# cataclysm-TOP.net
KiCad netlist of a schematic drawn in EAGLE
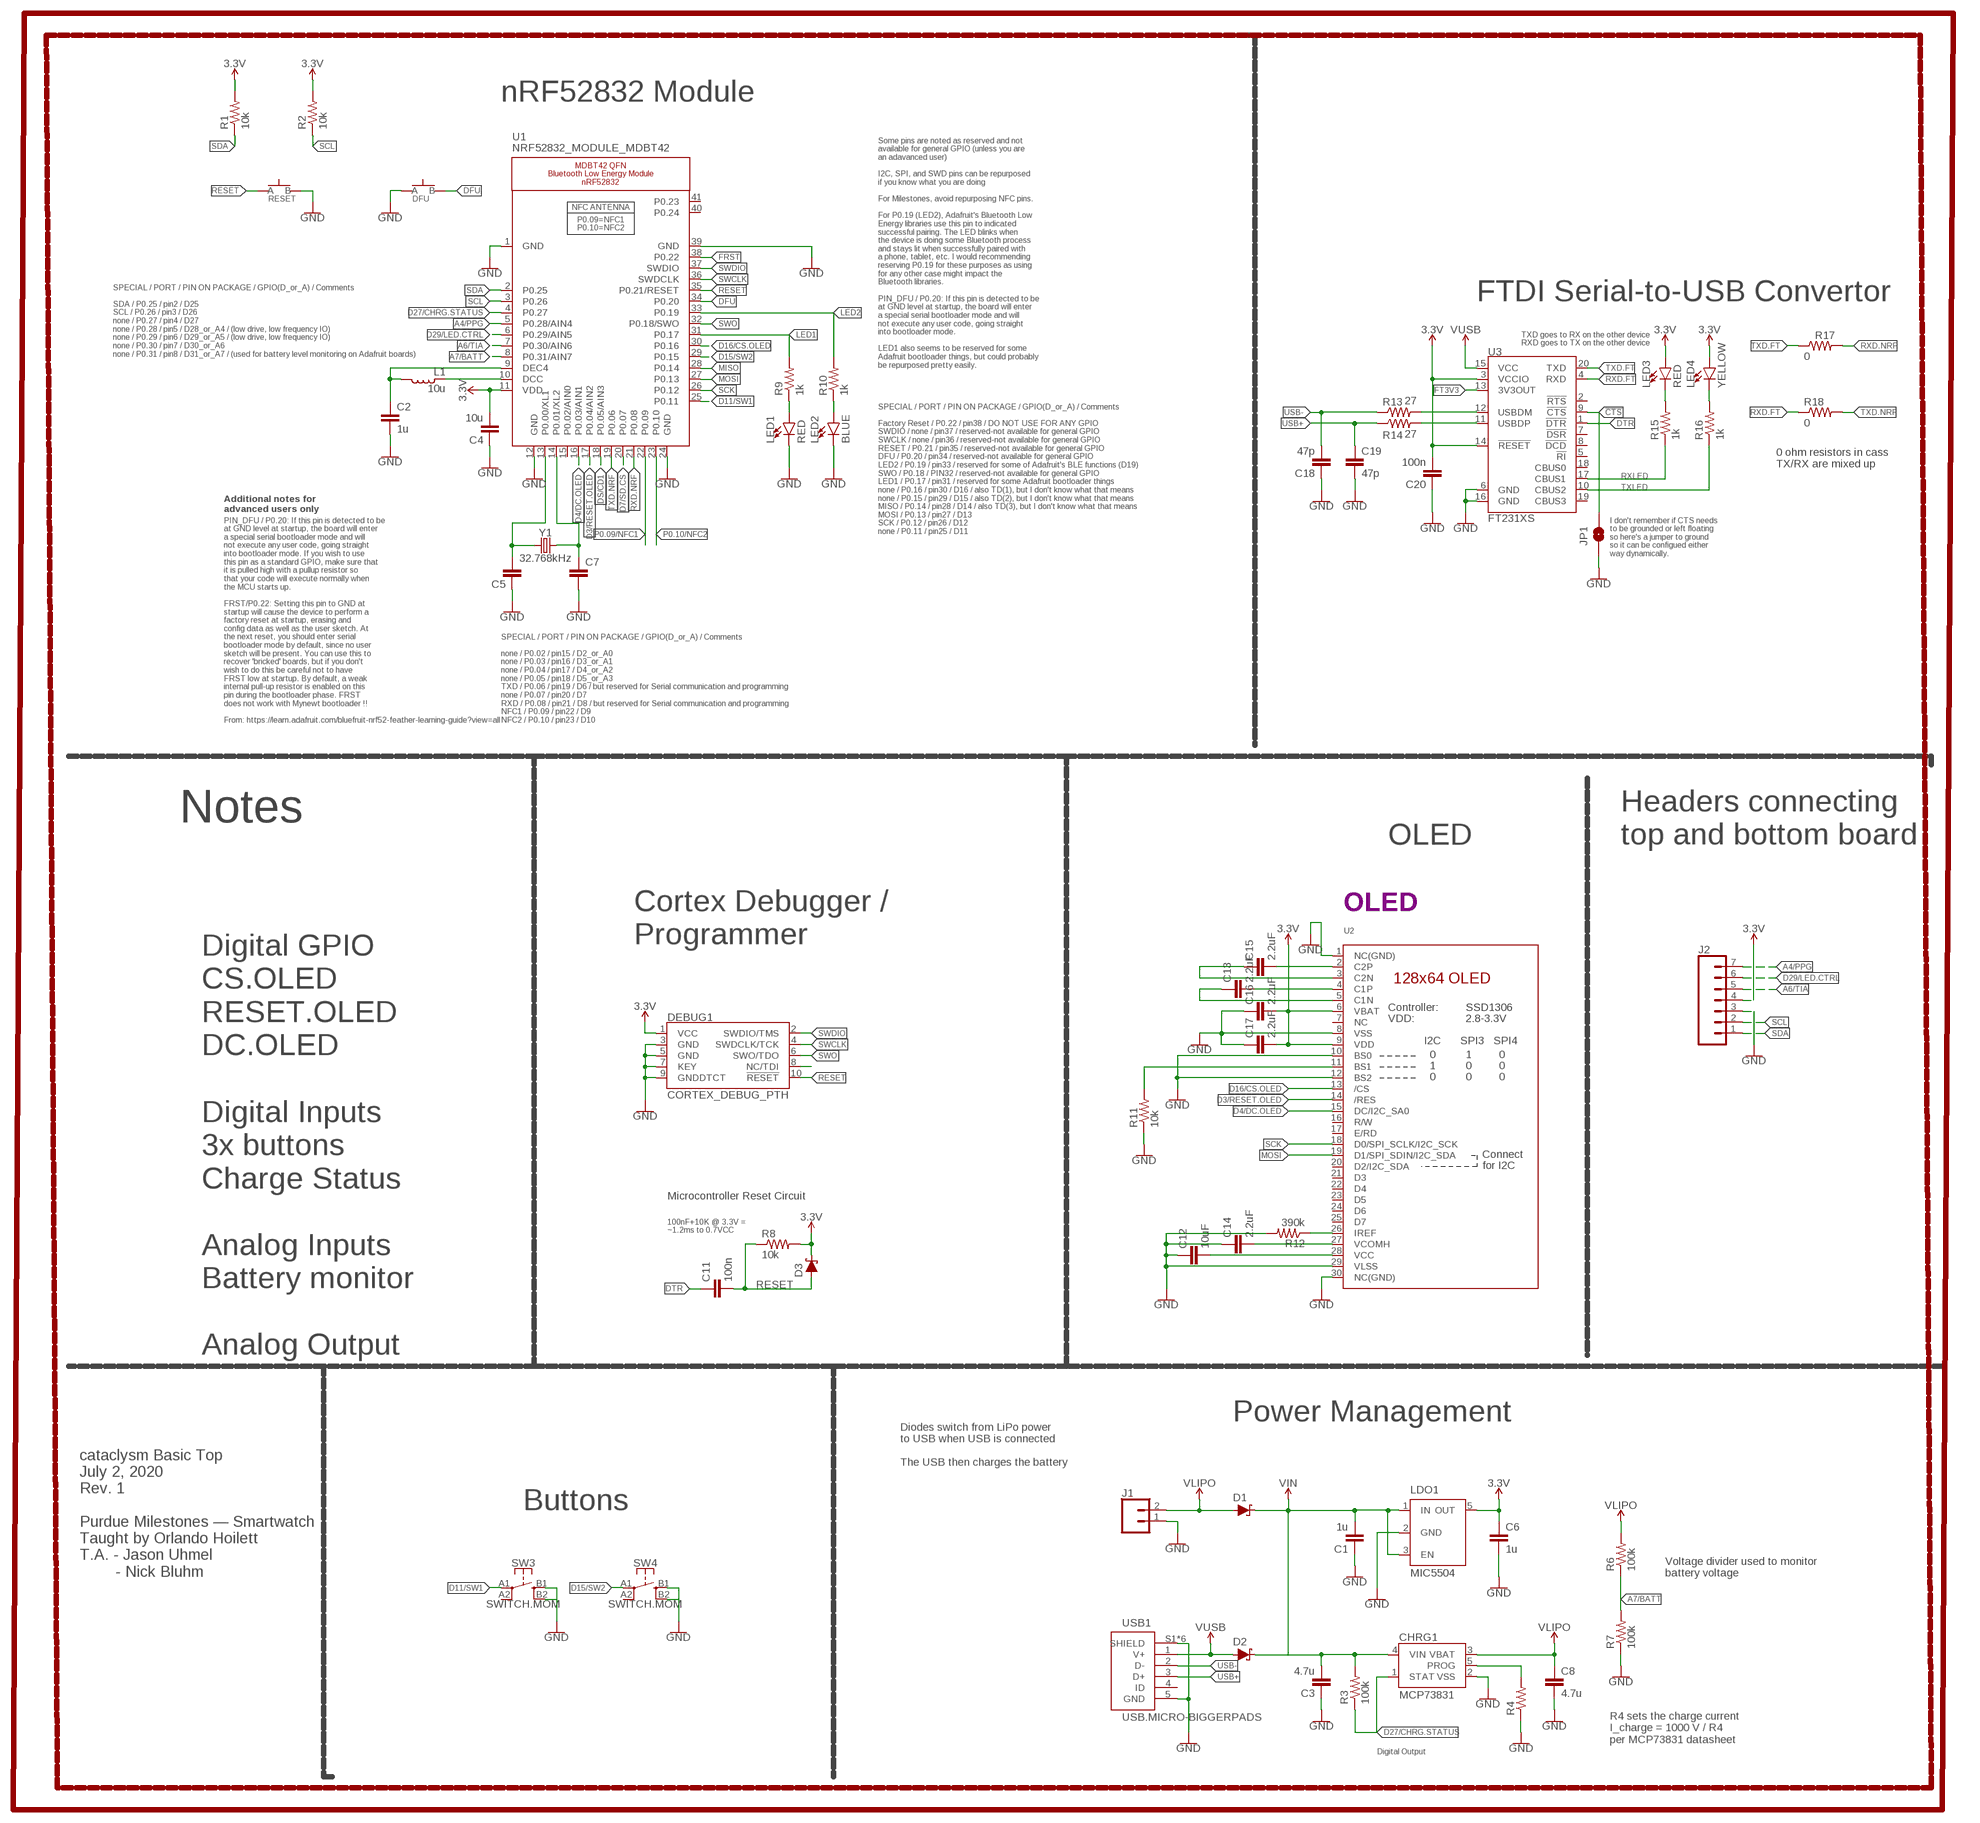
[diagram p0: schematic, sheet 1]

(export (version "E")
  (design (tool "Eeschema 10.0.6"))
  (components
    (comp (ref "C1")
      (value "1u")
      (footprint "eagle-import:C0603")
      (libsource (lib "eagle-import") (part "CAPACITOR0603"))
    )
    (comp (ref "C2")
      (value "1u")
      (footprint "eagle-import:C0603")
      (libsource (lib "eagle-import") (part "CAPACITOR0603"))
    )
    (comp (ref "C3")
      (value "4.7u")
      (footprint "eagle-import:C0603")
      (libsource (lib "eagle-import") (part "CAPACITOR0603"))
    )
    (comp (ref "C4")
      (value "10u")
      (footprint "eagle-import:C0805")
      (libsource (lib "eagle-import") (part "CAPACITOR0805"))
    )
    (comp (ref "C5")
      (value "CAPACITOR0603")
      (footprint "eagle-import:C0603")
      (libsource (lib "eagle-import") (part "CAPACITOR0603"))
    )
    (comp (ref "C6")
      (value "1u")
      (footprint "eagle-import:C0603")
      (libsource (lib "eagle-import") (part "CAPACITOR0603"))
    )
    (comp (ref "C7")
      (value "CAPACITOR0603")
      (footprint "eagle-import:C0603")
      (libsource (lib "eagle-import") (part "CAPACITOR0603"))
    )
    (comp (ref "C8")
      (value "4.7u")
      (footprint "eagle-import:C0603")
      (libsource (lib "eagle-import") (part "CAPACITOR0603"))
    )
    (comp (ref "C11")
      (value "100n")
      (footprint "eagle-import:C0603")
      (libsource (lib "eagle-import") (part "CAPACITOR0603"))
    )
    (comp (ref "C12")
      (value "10uF")
      (footprint "eagle-import:C0603")
      (libsource (lib "eagle-import") (part "CAPACITOR0603"))
    )
    (comp (ref "C13")
      (value "2.2uF")
      (footprint "eagle-import:C0402")
      (libsource (lib "eagle-import") (part "CAPACITOR0402"))
    )
    (comp (ref "C14")
      (value "2.2uF")
      (footprint "eagle-import:C0603")
      (libsource (lib "eagle-import") (part "CAPACITOR0603"))
    )
    (comp (ref "C15")
      (value "2.2uF")
      (footprint "eagle-import:C0402")
      (libsource (lib "eagle-import") (part "CAPACITOR0402"))
    )
    (comp (ref "C16")
      (value "2.2uF")
      (footprint "eagle-import:C0402")
      (libsource (lib "eagle-import") (part "CAPACITOR0402"))
    )
    (comp (ref "C17")
      (value "2.2uF")
      (footprint "eagle-import:C0402")
      (libsource (lib "eagle-import") (part "CAPACITOR0402"))
    )
    (comp (ref "C18")
      (value "47p")
      (footprint "eagle-import:C0603")
      (libsource (lib "eagle-import") (part "CAPACITOR0603"))
    )
    (comp (ref "C19")
      (value "47p")
      (footprint "eagle-import:C0603")
      (libsource (lib "eagle-import") (part "CAPACITOR0603"))
    )
    (comp (ref "C20")
      (value "100n")
      (footprint "eagle-import:C0603")
      (libsource (lib "eagle-import") (part "CAPACITOR0603"))
    )
    (comp (ref "CHRG1")
      (value "MCP73831")
      (footprint "eagle-import:SOT23-5")
      (libsource (lib "eagle-import") (part "MCP73831"))
    )
    (comp (ref "D1")
      (value "SCHOTTKY-USC")
      (footprint "eagle-import:USC")
      (libsource (lib "eagle-import") (part "SCHOTTKY-USC"))
    )
    (comp (ref "D2")
      (value "SCHOTTKY-USC")
      (footprint "eagle-import:USC")
      (libsource (lib "eagle-import") (part "SCHOTTKY-USC"))
    )
    (comp (ref "D3")
      (value "SCHOTTKY-USC")
      (footprint "eagle-import:USC")
      (libsource (lib "eagle-import") (part "SCHOTTKY-USC"))
    )
    (comp (ref "DEBUG1")
      (value "CORTEX_DEBUG_PTH")
      (footprint "eagle-import:2X5-PTH-1.27MM")
      (libsource (lib "eagle-import") (part "CORTEX_DEBUG_PTH"))
    )
    (comp (ref "DFU")
      (value "SPST-PTS830GG140-COPY.1-3")
      (footprint "eagle-import:BUTTON-GULLWING")
      (libsource (lib "eagle-import") (part "SPST-PTS830GG140-COPY.1-3"))
    )
    (comp (ref "J1")
      (value "CONN_02")
      (footprint "eagle-import:1X02")
      (libsource (lib "eagle-import") (part "CONN_02"))
    )
    (comp (ref "J2")
      (value "CONN_07-1.27MM")
      (footprint "eagle-import:1X07_1.27MM")
      (libsource (lib "eagle-import") (part "CONN_07-1.27MM"))
    )
    (comp (ref "JP1")
      (value "JUMPER-SMT_2_NO_SILK")
      (footprint "eagle-import:SMT-JUMPER_2_NO_SILK")
      (libsource (lib "eagle-import") (part "JUMPER-SMT_2_NO_SILK"))
    )
    (comp (ref "L1")
      (value "10u")
      (footprint "eagle-import:L0603")
      (libsource (lib "eagle-import") (part "INDUCTOR0603"))
    )
    (comp (ref "LDO1")
      (value "MIC5504")
      (footprint "eagle-import:SOT23-5")
      (libsource (lib "eagle-import") (part "MIC5504"))
    )
    (comp (ref "LED1")
      (value "RED")
      (footprint "eagle-import:LED-0603")
      (libsource (lib "eagle-import") (part "LED0603"))
    )
    (comp (ref "LED2")
      (value "BLUE")
      (footprint "eagle-import:LED-0603")
      (libsource (lib "eagle-import") (part "LED0603"))
    )
    (comp (ref "LED3")
      (value "RED")
      (footprint "eagle-import:LED-0603")
      (libsource (lib "eagle-import") (part "LED0603"))
    )
    (comp (ref "LED4")
      (value "YELLOW")
      (footprint "eagle-import:LED-0603")
      (libsource (lib "eagle-import") (part "LED0603"))
    )
    (comp (ref "R1")
      (value "10k")
      (footprint "eagle-import:R0603")
      (libsource (lib "eagle-import") (part "RESISTOR0603"))
    )
    (comp (ref "R2")
      (value "10k")
      (footprint "eagle-import:R0603")
      (libsource (lib "eagle-import") (part "RESISTOR0603"))
    )
    (comp (ref "R3")
      (value "100k")
      (footprint "eagle-import:R0603")
      (libsource (lib "eagle-import") (part "RESISTOR0603"))
    )
    (comp (ref "R4")
      (value "RESISTOR0603")
      (footprint "eagle-import:R0603")
      (libsource (lib "eagle-import") (part "RESISTOR0603"))
    )
    (comp (ref "R6")
      (value "100k")
      (footprint "eagle-import:R0603")
      (libsource (lib "eagle-import") (part "RESISTOR0603"))
    )
    (comp (ref "R7")
      (value "100k")
      (footprint "eagle-import:R0603")
      (libsource (lib "eagle-import") (part "RESISTOR0603"))
    )
    (comp (ref "R8")
      (value "10k")
      (footprint "eagle-import:R0603")
      (libsource (lib "eagle-import") (part "RESISTOR0603"))
    )
    (comp (ref "R9")
      (value "1k")
      (footprint "eagle-import:R0603")
      (libsource (lib "eagle-import") (part "RESISTOR0603"))
    )
    (comp (ref "R10")
      (value "1k")
      (footprint "eagle-import:R0603")
      (libsource (lib "eagle-import") (part "RESISTOR0603"))
    )
    (comp (ref "R11")
      (value "10k")
      (footprint "eagle-import:R0603")
      (libsource (lib "eagle-import") (part "RESISTOR0603"))
    )
    (comp (ref "R12")
      (value "390k")
      (footprint "eagle-import:R0603")
      (libsource (lib "eagle-import") (part "RESISTOR0603"))
    )
    (comp (ref "R13")
      (value "27")
      (footprint "eagle-import:R0603")
      (libsource (lib "eagle-import") (part "RESISTOR0603"))
    )
    (comp (ref "R14")
      (value "27")
      (footprint "eagle-import:R0603")
      (libsource (lib "eagle-import") (part "RESISTOR0603"))
    )
    (comp (ref "R15")
      (value "1k")
      (footprint "eagle-import:R0603")
      (libsource (lib "eagle-import") (part "RESISTOR0603"))
    )
    (comp (ref "R16")
      (value "1k")
      (footprint "eagle-import:R0603")
      (libsource (lib "eagle-import") (part "RESISTOR0603"))
    )
    (comp (ref "R17")
      (value "0")
      (footprint "eagle-import:R0603")
      (libsource (lib "eagle-import") (part "RESISTOR0603"))
    )
    (comp (ref "R18")
      (value "0")
      (footprint "eagle-import:R0603")
      (libsource (lib "eagle-import") (part "RESISTOR0603"))
    )
    (comp (ref "RESET")
      (value "SPST-PTS830GG140-COPY.1-3")
      (footprint "eagle-import:BUTTON-GULLWING")
      (libsource (lib "eagle-import") (part "SPST-PTS830GG140-COPY.1-3"))
    )
    (comp (ref "SW3")
      (value "SWITCH.MOM")
      (footprint "eagle-import:TACTILE_SWITCH_SMD_6.2MM_TALL")
      (libsource (lib "eagle-import") (part "SWITCH.MOM"))
    )
    (comp (ref "SW4")
      (value "SWITCH.MOM")
      (footprint "eagle-import:TACTILE_SWITCH_SMD_6.2MM_TALL")
      (libsource (lib "eagle-import") (part "SWITCH.MOM"))
    )
    (comp (ref "U1")
      (value "NRF52832_MODULE_MDBT42")
      (footprint "eagle-import:BLE_MODULE_RAYTAC_MDBT42")
      (libsource (lib "eagle-import") (part "NRF52832_MODULE_MDBT42"))
    )
    (comp (ref "U2")
      (value "DISP_OLED_UG-2864HSWEG01-NO-WRAPAROUND")
      (footprint "eagle-import:UG-2864HSWEG01_0.96IN_NO-WRAPAROUND")
      (libsource (lib "eagle-import") (part "DISP_OLED_UG-2864HSWEG01-NO-WRAPAROUND"))
    )
    (comp (ref "U3")
      (value "FT231XS")
      (footprint "eagle-import:SSOP20_L")
      (libsource (lib "eagle-import") (part "FT231XS"))
    )
    (comp (ref "USB1")
      (value "USB.MICRO-BIGGERPADS")
      (footprint "eagle-import:USB-MICRO-01.BIGGERPADS")
      (libsource (lib "eagle-import") (part "USB.MICRO-BIGGERPADS"))
    )
    (comp (ref "Y1")
      (value "32.768kHz")
      (footprint "eagle-import:2-SMD.NOLEAD.2.0MMTO1.2MM")
      (libsource (lib "eagle-import") (part "CRYSTALECS-.327-12.5-12-C-TR"))
    )
  )
  (nets
    (net (code "1") (name "/RXLED") (class "Default")
      (node (ref "R15") (pin "1") (pinfunction "1_1") (pintype "passive"))
      (node (ref "U3") (pin "17") (pinfunction "CBUS1_17") (pintype "bidirectional"))
    )
    (net (code "2") (name "/TXLED") (class "Default")
      (node (ref "R16") (pin "1") (pinfunction "1_1") (pintype "passive"))
      (node (ref "U3") (pin "10") (pinfunction "CBUS2_10") (pintype "bidirectional"))
    )
    (net (code "3") (name "/~{CTS}") (class "Default")
      (node (ref "JP1") (pin "2") (pinfunction "2_2") (pintype "passive"))
      (node (ref "U3") (pin "9") (pinfunction "~{CTS}_9") (pintype "bidirectional"))
    )
    (net (code "4") (name "3.3V") (class "Default")
      (node (ref "C16") (pin "2") (pinfunction "2_2") (pintype "passive"))
      (node (ref "C17") (pin "2") (pinfunction "2_2") (pintype "passive"))
      (node (ref "C20") (pin "2") (pinfunction "2_2") (pintype "passive"))
      (node (ref "C4") (pin "2") (pinfunction "2_2") (pintype "passive"))
      (node (ref "C6") (pin "1") (pinfunction "1_1") (pintype "passive"))
      (node (ref "D3") (pin "-") (pinfunction "C_-") (pintype "passive"))
      (node (ref "DEBUG1") (pin "1") (pinfunction "VCC_1") (pintype "bidirectional"))
      (node (ref "J2") (pin "4") (pinfunction "4_4") (pintype "passive"))
      (node (ref "LDO1") (pin "5") (pinfunction "OUT_5") (pintype "bidirectional"))
      (node (ref "LED3") (pin "A") (pinfunction "A_A") (pintype "passive"))
      (node (ref "LED4") (pin "A") (pinfunction "A_A") (pintype "passive"))
      (node (ref "R1") (pin "2") (pinfunction "2_2") (pintype "passive"))
      (node (ref "R2") (pin "2") (pinfunction "2_2") (pintype "passive"))
      (node (ref "R8") (pin "2") (pinfunction "2_2") (pintype "passive"))
      (node (ref "U1") (pin "11") (pinfunction "VDD_11") (pintype "bidirectional"))
      (node (ref "U2") (pin "6") (pinfunction "VBAT_6") (pintype "input"))
      (node (ref "U2") (pin "9") (pinfunction "VDD_9") (pintype "power_in"))
      (node (ref "U3") (pin "14") (pinfunction "~{RESET}_14") (pintype "bidirectional"))
      (node (ref "U3") (pin "3") (pinfunction "VCCIO_3") (pintype "bidirectional"))
    )
    (net (code "5") (name "A4{slash}PPG") (class "Default")
      (node (ref "J2") (pin "7") (pinfunction "7_7") (pintype "passive"))
      (node (ref "U1") (pin "5") (pinfunction "P0.28/AIN4_5") (pintype "bidirectional"))
    )
    (net (code "6") (name "A6{slash}TIA") (class "Default")
      (node (ref "J2") (pin "5") (pinfunction "5_5") (pintype "passive"))
      (node (ref "U1") (pin "7") (pinfunction "P0.30/AIN6_7") (pintype "bidirectional"))
    )
    (net (code "7") (name "A7{slash}BATT") (class "Default")
      (node (ref "R6") (pin "1") (pinfunction "1_1") (pintype "passive"))
      (node (ref "R7") (pin "2") (pinfunction "2_2") (pintype "passive"))
      (node (ref "U1") (pin "8") (pinfunction "P0.31/AIN7_8") (pintype "bidirectional"))
    )
    (net (code "8") (name "D3{slash}RESET.OLED") (class "Default")
      (node (ref "U1") (pin "17") (pinfunction "P0.04/AIN2_17") (pintype "bidirectional"))
      (node (ref "U2") (pin "14") (pinfunction "/RES_14") (pintype "input"))
    )
    (net (code "9") (name "D4{slash}DC.OLED") (class "Default")
      (node (ref "U1") (pin "16") (pinfunction "P0.03/AIN1_16") (pintype "bidirectional"))
      (node (ref "U2") (pin "15") (pinfunction "DC/I2C_SA0_15") (pintype "input"))
    )
    (net (code "10") (name "D7{slash}SD.CS") (class "Default")
      (node (ref "U1") (pin "20") (pinfunction "P0.07_20") (pintype "bidirectional"))
    )
    (net (code "11") (name "D11{slash}SW1") (class "Default")
      (node (ref "SW3") (pin "A1") (pinfunction "1_A1") (pintype "passive"))
      (node (ref "U1") (pin "25") (pinfunction "P0.11_25") (pintype "bidirectional"))
    )
    (net (code "12") (name "D15{slash}SW2") (class "Default")
      (node (ref "SW4") (pin "A1") (pinfunction "1_A1") (pintype "passive"))
      (node (ref "U1") (pin "29") (pinfunction "P0.15_29") (pintype "bidirectional"))
    )
    (net (code "13") (name "D16{slash}CS.OLED") (class "Default")
      (node (ref "U1") (pin "30") (pinfunction "P0.16_30") (pintype "bidirectional"))
      (node (ref "U2") (pin "13") (pinfunction "/CS_13") (pintype "input"))
    )
    (net (code "14") (name "D27{slash}CHRG.STATUS") (class "Default")
      (node (ref "CHRG1") (pin "1") (pinfunction "STAT_1") (pintype "output"))
      (node (ref "R3") (pin "1") (pinfunction "1_1") (pintype "passive"))
      (node (ref "U1") (pin "4") (pinfunction "P0.27_4") (pintype "bidirectional"))
    )
    (net (code "15") (name "D29{slash}LED.CTRL") (class "Default")
      (node (ref "J2") (pin "6") (pinfunction "6_6") (pintype "passive"))
      (node (ref "U1") (pin "6") (pinfunction "P0.29/AIN5_6") (pintype "bidirectional"))
    )
    (net (code "16") (name "DFU") (class "Default")
      (node (ref "DFU") (pin "3") (pinfunction "B_3") (pintype "bidirectional"))
      (node (ref "U1") (pin "34") (pinfunction "P0.20_34") (pintype "bidirectional"))
    )
    (net (code "17") (name "DS{slash}CD1") (class "Default")
      (node (ref "U1") (pin "18") (pinfunction "P0.05/AIN3_18") (pintype "bidirectional"))
    )
    (net (code "18") (name "DTR") (class "Default")
      (node (ref "C11") (pin "1") (pinfunction "1_1") (pintype "passive"))
      (node (ref "U3") (pin "1") (pinfunction "~{DTR}_1") (pintype "bidirectional"))
    )
    (net (code "19") (name "FRST") (class "Default")
      (node (ref "U1") (pin "38") (pinfunction "P0.22_38") (pintype "bidirectional"))
    )
    (net (code "20") (name "FT3V3") (class "Default")
      (node (ref "U3") (pin "13") (pinfunction "3V3OUT_13") (pintype "bidirectional"))
    )
    (net (code "21") (name "GND") (class "Default")
      (node (ref "C1") (pin "1") (pinfunction "1_1") (pintype "passive"))
      (node (ref "C12") (pin "1") (pinfunction "1_1") (pintype "passive"))
      (node (ref "C14") (pin "1") (pinfunction "1_1") (pintype "passive"))
      (node (ref "C16") (pin "1") (pinfunction "1_1") (pintype "passive"))
      (node (ref "C17") (pin "1") (pinfunction "1_1") (pintype "passive"))
      (node (ref "C18") (pin "1") (pinfunction "1_1") (pintype "passive"))
      (node (ref "C19") (pin "2") (pinfunction "2_2") (pintype "passive"))
      (node (ref "C2") (pin "2") (pinfunction "2_2") (pintype "passive"))
      (node (ref "C20") (pin "1") (pinfunction "1_1") (pintype "passive"))
      (node (ref "C3") (pin "1") (pinfunction "1_1") (pintype "passive"))
      (node (ref "C4") (pin "1") (pinfunction "1_1") (pintype "passive"))
      (node (ref "C5") (pin "1") (pinfunction "1_1") (pintype "passive"))
      (node (ref "C6") (pin "2") (pinfunction "2_2") (pintype "passive"))
      (node (ref "C7") (pin "2") (pinfunction "2_2") (pintype "passive"))
      (node (ref "C8") (pin "2") (pinfunction "2_2") (pintype "passive"))
      (node (ref "CHRG1") (pin "2") (pinfunction "VSS_2") (pintype "power_in"))
      (node (ref "DEBUG1") (pin "3") (pinfunction "GND_3") (pintype "bidirectional"))
      (node (ref "DEBUG1") (pin "5") (pinfunction "GND_5") (pintype "bidirectional"))
      (node (ref "DEBUG1") (pin "7") (pinfunction "KEY_7") (pintype "bidirectional"))
      (node (ref "DEBUG1") (pin "9") (pinfunction "GNDDTCT_9") (pintype "bidirectional"))
      (node (ref "DFU") (pin "1") (pinfunction "A_1") (pintype "bidirectional"))
      (node (ref "J1") (pin "1") (pinfunction "1_1") (pintype "passive"))
      (node (ref "J2") (pin "3") (pinfunction "3_3") (pintype "passive"))
      (node (ref "JP1") (pin "1") (pinfunction "1_1") (pintype "passive"))
      (node (ref "LDO1") (pin "2") (pinfunction "GND_2") (pintype "bidirectional"))
      (node (ref "LED1") (pin "C") (pinfunction "C_C") (pintype "passive"))
      (node (ref "LED2") (pin "C") (pinfunction "C_C") (pintype "passive"))
      (node (ref "R11") (pin "1") (pinfunction "1_1") (pintype "passive"))
      (node (ref "R12") (pin "2") (pinfunction "2_2") (pintype "passive"))
      (node (ref "R4") (pin "1") (pinfunction "1_1") (pintype "passive"))
      (node (ref "R7") (pin "1") (pinfunction "1_1") (pintype "passive"))
      (node (ref "RESET") (pin "3") (pinfunction "B_3") (pintype "bidirectional"))
      (node (ref "SW3") (pin "B1") (pinfunction "3_B1") (pintype "passive"))
      (node (ref "SW4") (pin "B1") (pinfunction "3_B1") (pintype "passive"))
      (node (ref "U1") (pin "1") (pinfunction "GND_1") (pintype "bidirectional"))
      (node (ref "U1") (pin "12") (pinfunction "GND_12") (pintype "bidirectional"))
      (node (ref "U1") (pin "24") (pinfunction "GND_24") (pintype "bidirectional"))
      (node (ref "U1") (pin "39") (pinfunction "GND_39") (pintype "bidirectional"))
      (node (ref "U2") (pin "1") (pinfunction "NC(GND)_1") (pintype "input"))
      (node (ref "U2") (pin "10") (pinfunction "BS0_10") (pintype "input"))
      (node (ref "U2") (pin "12") (pinfunction "BS2_12") (pintype "input"))
      (node (ref "U2") (pin "29") (pinfunction "VLSS_29") (pintype "power_in"))
      (node (ref "U2") (pin "30") (pinfunction "NC(GND)_30") (pintype "input"))
      (node (ref "U2") (pin "8") (pinfunction "VSS_8") (pintype "power_in"))
      (node (ref "U3") (pin "16") (pinfunction "GND_16") (pintype "bidirectional"))
      (node (ref "U3") (pin "6") (pinfunction "GND_6") (pintype "bidirectional"))
      (node (ref "USB1") (pin "5") (pinfunction "GND_5") (pintype "bidirectional"))
      (node (ref "USB1") (pin "S1") (pinfunction "SHIELD_S1") (pintype "bidirectional"))
      (node (ref "USB1") (pin "S2") (pinfunction "SHIELD_S2") (pintype "bidirectional"))
      (node (ref "USB1") (pin "S3") (pinfunction "SHIELD_S3") (pintype "bidirectional"))
      (node (ref "USB1") (pin "S4") (pinfunction "SHIELD_S4") (pintype "bidirectional"))
      (node (ref "USB1") (pin "S5") (pinfunction "SHIELD_S5") (pintype "bidirectional"))
      (node (ref "USB1") (pin "S6") (pinfunction "SHIELD_S6") (pintype "bidirectional"))
    )
    (net (code "22") (name "LED1") (class "Default")
      (node (ref "R9") (pin "2") (pinfunction "2_2") (pintype "passive"))
      (node (ref "U1") (pin "31") (pinfunction "P0.17_31") (pintype "bidirectional"))
    )
    (net (code "23") (name "LED2") (class "Default")
      (node (ref "R10") (pin "2") (pinfunction "2_2") (pintype "passive"))
      (node (ref "U1") (pin "33") (pinfunction "P0.19_33") (pintype "bidirectional"))
    )
    (net (code "24") (name "MISO") (class "Default")
      (node (ref "U1") (pin "28") (pinfunction "P0.14_28") (pintype "bidirectional"))
    )
    (net (code "25") (name "MOSI") (class "Default")
      (node (ref "U1") (pin "27") (pinfunction "P0.13_27") (pintype "bidirectional"))
      (node (ref "U2") (pin "19") (pinfunction "D1/SPI_SDIN/I2C_SDA_19") (pintype "bidirectional"))
    )
    (net (code "26") (name "Net-(CHRG1-PROG)") (class "Default")
      (node (ref "CHRG1") (pin "5") (pinfunction "PROG_5") (pintype "input"))
      (node (ref "R4") (pin "2") (pinfunction "2_2") (pintype "passive"))
    )
    (net (code "27") (name "Net-(LED1-PadA)") (class "Default")
      (node (ref "LED1") (pin "A") (pinfunction "A_A") (pintype "passive"))
      (node (ref "R9") (pin "1") (pinfunction "1_1") (pintype "passive"))
    )
    (net (code "28") (name "Net-(LED2-PadA)") (class "Default")
      (node (ref "LED2") (pin "A") (pinfunction "A_A") (pintype "passive"))
      (node (ref "R10") (pin "1") (pinfunction "1_1") (pintype "passive"))
    )
    (net (code "29") (name "Net-(LED3-PadC)") (class "Default")
      (node (ref "LED3") (pin "C") (pinfunction "C_C") (pintype "passive"))
      (node (ref "R15") (pin "2") (pinfunction "2_2") (pintype "passive"))
    )
    (net (code "30") (name "Net-(LED4-PadC)") (class "Default")
      (node (ref "LED4") (pin "C") (pinfunction "C_C") (pintype "passive"))
      (node (ref "R16") (pin "2") (pinfunction "2_2") (pintype "passive"))
    )
    (net (code "31") (name "Net-(U1-DCC)") (class "Default")
      (node (ref "L1") (pin "1") (pinfunction "1_1") (pintype "passive"))
      (node (ref "U1") (pin "10") (pinfunction "DCC_10") (pintype "bidirectional"))
    )
    (net (code "32") (name "Net-(U1-DEC4)") (class "Default")
      (node (ref "C2") (pin "1") (pinfunction "1_1") (pintype "passive"))
      (node (ref "L1") (pin "2") (pinfunction "2_2") (pintype "passive"))
      (node (ref "U1") (pin "9") (pinfunction "DEC4_9") (pintype "bidirectional"))
    )
    (net (code "33") (name "Net-(U1-P0.00{slash}XL1)") (class "Default")
      (node (ref "C5") (pin "2") (pinfunction "2_2") (pintype "passive"))
      (node (ref "U1") (pin "13") (pinfunction "P0.00/XL1_13") (pintype "bidirectional"))
      (node (ref "Y1") (pin "P$1") (pinfunction "1_P$1") (pintype "passive"))
    )
    (net (code "34") (name "Net-(U1-P0.01{slash}XL2)") (class "Default")
      (node (ref "C7") (pin "1") (pinfunction "1_1") (pintype "passive"))
      (node (ref "U1") (pin "14") (pinfunction "P0.01/XL2_14") (pintype "bidirectional"))
      (node (ref "Y1") (pin "P$2") (pinfunction "2_P$2") (pintype "passive"))
    )
    (net (code "35") (name "Net-(U2-BS1)") (class "Default")
      (node (ref "R11") (pin "2") (pinfunction "2_2") (pintype "passive"))
      (node (ref "U2") (pin "11") (pinfunction "BS1_11") (pintype "input"))
    )
    (net (code "36") (name "Net-(U2-C1N)") (class "Default")
      (node (ref "C13") (pin "1") (pinfunction "1_1") (pintype "passive"))
      (node (ref "U2") (pin "5") (pinfunction "C1N_5") (pintype "input"))
    )
    (net (code "37") (name "Net-(U2-C1P)") (class "Default")
      (node (ref "C13") (pin "2") (pinfunction "2_2") (pintype "passive"))
      (node (ref "U2") (pin "4") (pinfunction "C1P_4") (pintype "input"))
    )
    (net (code "38") (name "Net-(U2-C2N)") (class "Default")
      (node (ref "C15") (pin "1") (pinfunction "1_1") (pintype "passive"))
      (node (ref "U2") (pin "3") (pinfunction "C2N_3") (pintype "input"))
    )
    (net (code "39") (name "Net-(U2-C2P)") (class "Default")
      (node (ref "C15") (pin "2") (pinfunction "2_2") (pintype "passive"))
      (node (ref "U2") (pin "2") (pinfunction "C2P_2") (pintype "input"))
    )
    (net (code "40") (name "Net-(U2-IREF)") (class "Default")
      (node (ref "R12") (pin "1") (pinfunction "1_1") (pintype "passive"))
      (node (ref "U2") (pin "26") (pinfunction "IREF_26") (pintype "input"))
    )
    (net (code "41") (name "Net-(U2-VCC)") (class "Default")
      (node (ref "C12") (pin "2") (pinfunction "2_2") (pintype "passive"))
      (node (ref "U2") (pin "28") (pinfunction "VCC_28") (pintype "power_in"))
    )
    (net (code "42") (name "Net-(U2-VCOMH)") (class "Default")
      (node (ref "C14") (pin "2") (pinfunction "2_2") (pintype "passive"))
      (node (ref "U2") (pin "27") (pinfunction "VCOMH_27") (pintype "output"))
    )
    (net (code "43") (name "Net-(U3-USBDM)") (class "Default")
      (node (ref "R13") (pin "2") (pinfunction "2_2") (pintype "passive"))
      (node (ref "U3") (pin "12") (pinfunction "USBDM_12") (pintype "bidirectional"))
    )
    (net (code "44") (name "Net-(U3-USBDP)") (class "Default")
      (node (ref "R14") (pin "2") (pinfunction "2_2") (pintype "passive"))
      (node (ref "U3") (pin "11") (pinfunction "USBDP_11") (pintype "bidirectional"))
    )
    (net (code "45") (name "P0.09{slash}NFC1") (class "Default")
      (node (ref "U1") (pin "22") (pinfunction "P0.09_22") (pintype "bidirectional"))
    )
    (net (code "46") (name "P0.10{slash}NFC2") (class "Default")
      (node (ref "U1") (pin "23") (pinfunction "P0.10_23") (pintype "bidirectional"))
    )
    (net (code "47") (name "RESET") (class "Default")
      (node (ref "C11") (pin "2") (pinfunction "2_2") (pintype "passive"))
      (node (ref "D3") (pin "+") (pinfunction "A_+") (pintype "passive"))
      (node (ref "DEBUG1") (pin "10") (pinfunction "~{RESET}_10") (pintype "bidirectional"))
      (node (ref "R8") (pin "1") (pinfunction "1_1") (pintype "passive"))
      (node (ref "RESET") (pin "1") (pinfunction "A_1") (pintype "bidirectional"))
      (node (ref "U1") (pin "35") (pinfunction "P0.21/RESET_35") (pintype "bidirectional"))
    )
    (net (code "48") (name "RXD.FT") (class "Default")
      (node (ref "R18") (pin "1") (pinfunction "1_1") (pintype "passive"))
      (node (ref "U3") (pin "4") (pinfunction "RXD_4") (pintype "bidirectional"))
    )
    (net (code "49") (name "RXD.NRF") (class "Default")
      (node (ref "R17") (pin "2") (pinfunction "2_2") (pintype "passive"))
      (node (ref "U1") (pin "21") (pinfunction "P0.08_21") (pintype "bidirectional"))
    )
    (net (code "50") (name "SCK") (class "Default")
      (node (ref "U1") (pin "26") (pinfunction "P0.12_26") (pintype "bidirectional"))
      (node (ref "U2") (pin "18") (pinfunction "D0/SPI_SCLK/I2C_SCK_18") (pintype "bidirectional"))
    )
    (net (code "51") (name "SCL") (class "Default")
      (node (ref "J2") (pin "2") (pinfunction "2_2") (pintype "passive"))
      (node (ref "R2") (pin "1") (pinfunction "1_1") (pintype "passive"))
      (node (ref "U1") (pin "3") (pinfunction "P0.26_3") (pintype "bidirectional"))
    )
    (net (code "52") (name "SDA") (class "Default")
      (node (ref "J2") (pin "1") (pinfunction "1_1") (pintype "passive"))
      (node (ref "R1") (pin "1") (pinfunction "1_1") (pintype "passive"))
      (node (ref "U1") (pin "2") (pinfunction "P0.25_2") (pintype "bidirectional"))
    )
    (net (code "53") (name "SWCLK") (class "Default")
      (node (ref "DEBUG1") (pin "4") (pinfunction "SWDCLK/TCK_4") (pintype "bidirectional"))
      (node (ref "U1") (pin "36") (pinfunction "SWDCLK_36") (pintype "bidirectional"))
    )
    (net (code "54") (name "SWDIO") (class "Default")
      (node (ref "DEBUG1") (pin "2") (pinfunction "SWDIO/TMS_2") (pintype "bidirectional"))
      (node (ref "U1") (pin "37") (pinfunction "SWDIO_37") (pintype "bidirectional"))
    )
    (net (code "55") (name "SWO") (class "Default")
      (node (ref "DEBUG1") (pin "6") (pinfunction "SWO/TDO_6") (pintype "bidirectional"))
      (node (ref "U1") (pin "32") (pinfunction "P0.18/SWO_32") (pintype "bidirectional"))
    )
    (net (code "56") (name "TXD.FT") (class "Default")
      (node (ref "R17") (pin "1") (pinfunction "1_1") (pintype "passive"))
      (node (ref "U3") (pin "20") (pinfunction "TXD_20") (pintype "bidirectional"))
    )
    (net (code "57") (name "TXD.NRF") (class "Default")
      (node (ref "R18") (pin "2") (pinfunction "2_2") (pintype "passive"))
      (node (ref "U1") (pin "19") (pinfunction "P0.06_19") (pintype "bidirectional"))
    )
    (net (code "58") (name "USB+") (class "Default")
      (node (ref "C19") (pin "1") (pinfunction "1_1") (pintype "passive"))
      (node (ref "R14") (pin "1") (pinfunction "1_1") (pintype "passive"))
      (node (ref "USB1") (pin "3") (pinfunction "D+_3") (pintype "bidirectional"))
    )
    (net (code "59") (name "USB-") (class "Default")
      (node (ref "C18") (pin "2") (pinfunction "2_2") (pintype "passive"))
      (node (ref "R13") (pin "1") (pinfunction "1_1") (pintype "passive"))
      (node (ref "USB1") (pin "2") (pinfunction "D-_2") (pintype "bidirectional"))
    )
    (net (code "60") (name "VIN") (class "Default")
      (node (ref "C1") (pin "2") (pinfunction "2_2") (pintype "passive"))
      (node (ref "C3") (pin "2") (pinfunction "2_2") (pintype "passive"))
      (node (ref "CHRG1") (pin "4") (pinfunction "VIN_4") (pintype "power_in"))
      (node (ref "D1") (pin "-") (pinfunction "C_-") (pintype "passive"))
      (node (ref "D2") (pin "-") (pinfunction "C_-") (pintype "passive"))
      (node (ref "LDO1") (pin "1") (pinfunction "IN_1") (pintype "bidirectional"))
      (node (ref "LDO1") (pin "3") (pinfunction "EN_3") (pintype "bidirectional"))
      (node (ref "R3") (pin "2") (pinfunction "2_2") (pintype "passive"))
    )
    (net (code "61") (name "VLIPO") (class "Default")
      (node (ref "C8") (pin "1") (pinfunction "1_1") (pintype "passive"))
      (node (ref "CHRG1") (pin "3") (pinfunction "VBAT_3") (pintype "power_in"))
      (node (ref "D1") (pin "+") (pinfunction "A_+") (pintype "passive"))
      (node (ref "J1") (pin "2") (pinfunction "2_2") (pintype "passive"))
      (node (ref "R6") (pin "2") (pinfunction "2_2") (pintype "passive"))
    )
    (net (code "62") (name "VUSB") (class "Default")
      (node (ref "D2") (pin "+") (pinfunction "A_+") (pintype "passive"))
      (node (ref "U3") (pin "15") (pinfunction "VCC_15") (pintype "bidirectional"))
      (node (ref "USB1") (pin "1") (pinfunction "V+_1") (pintype "bidirectional"))
    )
    (net (code "63") (name "unconnected-(DEBUG1-NC{slash}TDI-Pad8)") (class "Default")
      (node (ref "DEBUG1") (pin "8") (pinfunction "NC/TDI_8") (pintype "bidirectional"))
    )
    (net (code "64") (name "unconnected-(SW3-2-PadA2)") (class "Default")
      (node (ref "SW3") (pin "A2") (pinfunction "2_A2") (pintype "passive"))
    )
    (net (code "65") (name "unconnected-(SW3-4-PadB2)") (class "Default")
      (node (ref "SW3") (pin "B2") (pinfunction "4_B2") (pintype "passive"))
    )
    (net (code "66") (name "unconnected-(SW4-2-PadA2)") (class "Default")
      (node (ref "SW4") (pin "A2") (pinfunction "2_A2") (pintype "passive"))
    )
    (net (code "67") (name "unconnected-(SW4-4-PadB2)") (class "Default")
      (node (ref "SW4") (pin "B2") (pinfunction "4_B2") (pintype "passive"))
    )
    (net (code "68") (name "unconnected-(U1-P0.02{slash}AIN0-Pad15)") (class "Default")
      (node (ref "U1") (pin "15") (pinfunction "P0.02/AIN0_15") (pintype "bidirectional"))
    )
    (net (code "69") (name "unconnected-(U1-P0.23-Pad41)") (class "Default")
      (node (ref "U1") (pin "41") (pinfunction "P0.23_41") (pintype "bidirectional"))
    )
    (net (code "70") (name "unconnected-(U1-P0.24-Pad40)") (class "Default")
      (node (ref "U1") (pin "40") (pinfunction "P0.24_40") (pintype "bidirectional"))
    )
    (net (code "71") (name "unconnected-(U2-D2{slash}I2C_SDA-Pad20)") (class "Default")
      (node (ref "U2") (pin "20") (pinfunction "D2/I2C_SDA_20") (pintype "bidirectional"))
    )
    (net (code "72") (name "unconnected-(U2-D3-Pad21)") (class "Default")
      (node (ref "U2") (pin "21") (pinfunction "D3_21") (pintype "bidirectional"))
    )
    (net (code "73") (name "unconnected-(U2-D4-Pad22)") (class "Default")
      (node (ref "U2") (pin "22") (pinfunction "D4_22") (pintype "bidirectional"))
    )
    (net (code "74") (name "unconnected-(U2-D5-Pad23)") (class "Default")
      (node (ref "U2") (pin "23") (pinfunction "D5_23") (pintype "bidirectional"))
    )
    (net (code "75") (name "unconnected-(U2-D6-Pad24)") (class "Default")
      (node (ref "U2") (pin "24") (pinfunction "D6_24") (pintype "bidirectional"))
    )
    (net (code "76") (name "unconnected-(U2-D7-Pad25)") (class "Default")
      (node (ref "U2") (pin "25") (pinfunction "D7_25") (pintype "bidirectional"))
    )
    (net (code "77") (name "unconnected-(U2-E{slash}RD-Pad17)") (class "Default")
      (node (ref "U2") (pin "17") (pinfunction "E/RD_17") (pintype "input"))
    )
    (net (code "78") (name "unconnected-(U2-NC-Pad7)") (class "Default")
      (node (ref "U2") (pin "7") (pinfunction "NC_7") (pintype "no_connect"))
    )
    (net (code "79") (name "unconnected-(U2-R{slash}W-Pad16)") (class "Default")
      (node (ref "U2") (pin "16") (pinfunction "R/W_16") (pintype "input"))
    )
    (net (code "80") (name "unconnected-(U3-CBUS0-Pad18)") (class "Default")
      (node (ref "U3") (pin "18") (pinfunction "CBUS0_18") (pintype "bidirectional"))
    )
    (net (code "81") (name "unconnected-(U3-CBUS3-Pad19)") (class "Default")
      (node (ref "U3") (pin "19") (pinfunction "CBUS3_19") (pintype "bidirectional"))
    )
    (net (code "82") (name "unconnected-(U3-~{DCD}-Pad8)") (class "Default")
      (node (ref "U3") (pin "8") (pinfunction "~{DCD}_8") (pintype "bidirectional"))
    )
    (net (code "83") (name "unconnected-(U3-~{DSR}-Pad7)") (class "Default")
      (node (ref "U3") (pin "7") (pinfunction "~{DSR}_7") (pintype "bidirectional"))
    )
    (net (code "84") (name "unconnected-(U3-~{RI}-Pad5)") (class "Default")
      (node (ref "U3") (pin "5") (pinfunction "~{RI}_5") (pintype "bidirectional"))
    )
    (net (code "85") (name "unconnected-(U3-~{RTS}-Pad2)") (class "Default")
      (node (ref "U3") (pin "2") (pinfunction "~{RTS}_2") (pintype "bidirectional"))
    )
    (net (code "86") (name "unconnected-(USB1-ID-Pad4)") (class "Default")
      (node (ref "USB1") (pin "4") (pinfunction "ID_4") (pintype "bidirectional"))
    )
  )
)
